# Ring_5_B.net
KiCad netlist of a schematic drawn in Altium Designer
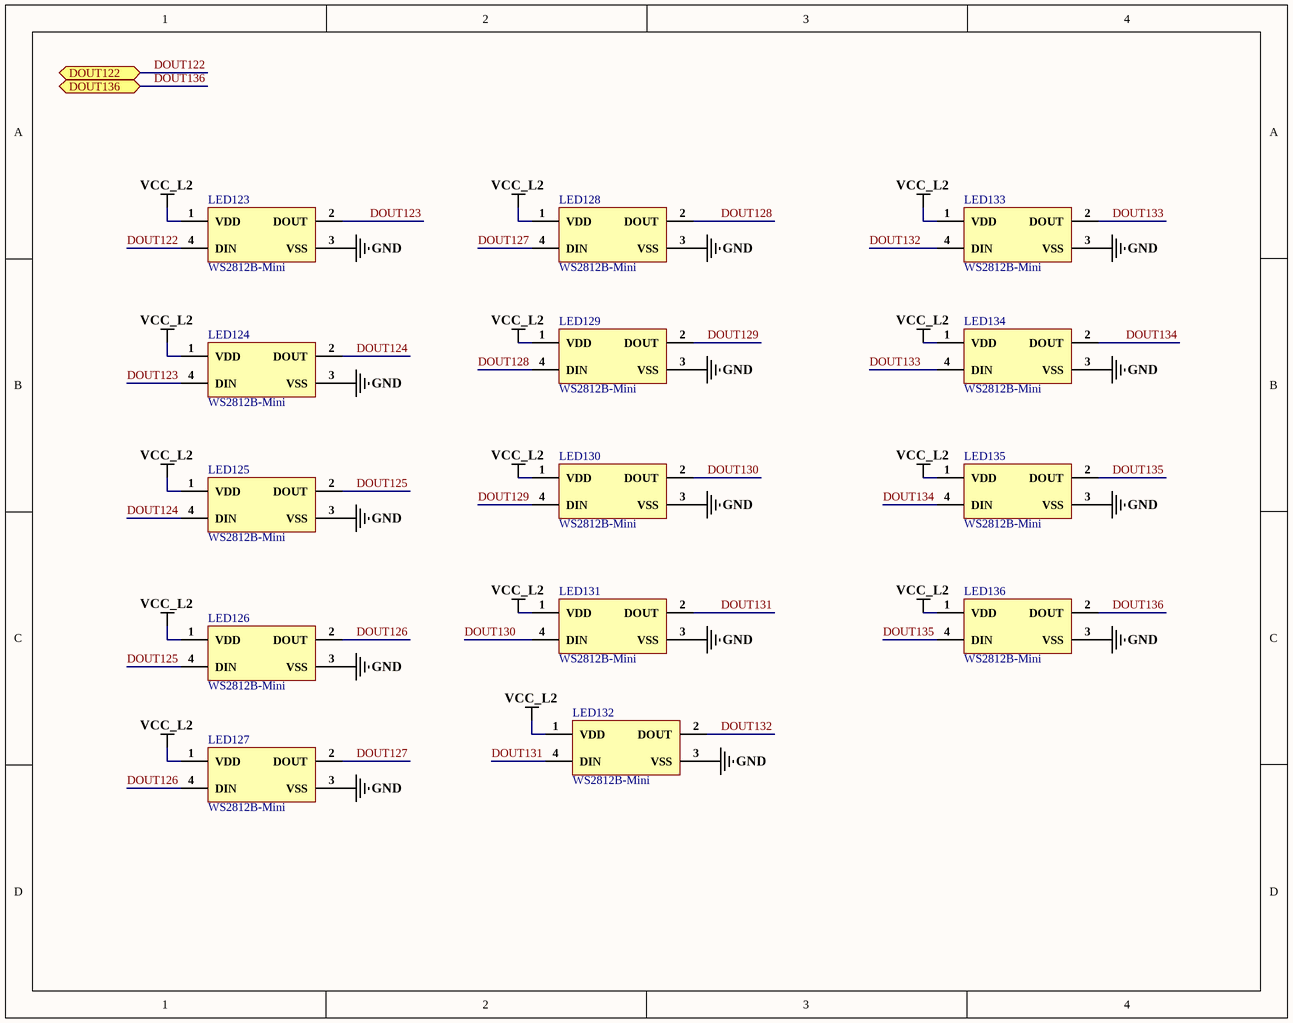
[diagram p0: Ring 5_B.SchDoc]

(export (version "E")
  (design (tool "Eeschema 10.0.6"))
  (components
    (comp (ref "LED123")
      (value "WS2812B-Mini")
      (footprint "WS2812B-Mini")
      (description "SMD,3.5x3.5mm Light Emitting Diodes (LED) RoHS")
      (fields (field (name "MANUFACTURER") "Worldsemi"))
      (libsource (lib "TT_IntLib") (part "WS2812B-Mini"))
    )
    (comp (ref "LED124")
      (value "WS2812B-Mini")
      (footprint "WS2812B-Mini")
      (description "SMD,3.5x3.5mm Light Emitting Diodes (LED) RoHS")
      (fields (field (name "MANUFACTURER") "Worldsemi"))
      (libsource (lib "TT_IntLib") (part "WS2812B-Mini"))
    )
    (comp (ref "LED125")
      (value "WS2812B-Mini")
      (footprint "WS2812B-Mini")
      (description "SMD,3.5x3.5mm Light Emitting Diodes (LED) RoHS")
      (fields (field (name "MANUFACTURER") "Worldsemi"))
      (libsource (lib "TT_IntLib") (part "WS2812B-Mini"))
    )
    (comp (ref "LED126")
      (value "WS2812B-Mini")
      (footprint "WS2812B-Mini")
      (description "SMD,3.5x3.5mm Light Emitting Diodes (LED) RoHS")
      (fields (field (name "MANUFACTURER") "Worldsemi"))
      (libsource (lib "TT_IntLib") (part "WS2812B-Mini"))
    )
    (comp (ref "LED127")
      (value "WS2812B-Mini")
      (footprint "WS2812B-Mini")
      (description "SMD,3.5x3.5mm Light Emitting Diodes (LED) RoHS")
      (fields (field (name "MANUFACTURER") "Worldsemi"))
      (libsource (lib "TT_IntLib") (part "WS2812B-Mini"))
    )
    (comp (ref "LED128")
      (value "WS2812B-Mini")
      (footprint "WS2812B-Mini")
      (description "SMD,3.5x3.5mm Light Emitting Diodes (LED) RoHS")
      (fields (field (name "MANUFACTURER") "Worldsemi"))
      (libsource (lib "TT_IntLib") (part "WS2812B-Mini"))
    )
    (comp (ref "LED129")
      (value "WS2812B-Mini")
      (footprint "WS2812B-Mini")
      (description "SMD,3.5x3.5mm Light Emitting Diodes (LED) RoHS")
      (fields (field (name "MANUFACTURER") "Worldsemi"))
      (libsource (lib "TT_IntLib") (part "WS2812B-Mini"))
    )
    (comp (ref "LED130")
      (value "WS2812B-Mini")
      (footprint "WS2812B-Mini")
      (description "SMD,3.5x3.5mm Light Emitting Diodes (LED) RoHS")
      (fields (field (name "MANUFACTURER") "Worldsemi"))
      (libsource (lib "TT_IntLib") (part "WS2812B-Mini"))
    )
    (comp (ref "LED131")
      (value "WS2812B-Mini")
      (footprint "WS2812B-Mini")
      (description "SMD,3.5x3.5mm Light Emitting Diodes (LED) RoHS")
      (fields (field (name "MANUFACTURER") "Worldsemi"))
      (libsource (lib "TT_IntLib") (part "WS2812B-Mini"))
    )
    (comp (ref "LED132")
      (value "WS2812B-Mini")
      (footprint "WS2812B-Mini")
      (description "SMD,3.5x3.5mm Light Emitting Diodes (LED) RoHS")
      (fields (field (name "MANUFACTURER") "Worldsemi"))
      (libsource (lib "TT_IntLib") (part "WS2812B-Mini"))
    )
    (comp (ref "LED133")
      (value "WS2812B-Mini")
      (footprint "WS2812B-Mini")
      (description "SMD,3.5x3.5mm Light Emitting Diodes (LED) RoHS")
      (fields (field (name "MANUFACTURER") "Worldsemi"))
      (libsource (lib "TT_IntLib") (part "WS2812B-Mini"))
    )
    (comp (ref "LED134")
      (value "WS2812B-Mini")
      (footprint "WS2812B-Mini")
      (description "SMD,3.5x3.5mm Light Emitting Diodes (LED) RoHS")
      (fields (field (name "MANUFACTURER") "Worldsemi"))
      (libsource (lib "TT_IntLib") (part "WS2812B-Mini"))
    )
    (comp (ref "LED135")
      (value "WS2812B-Mini")
      (footprint "WS2812B-Mini")
      (description "SMD,3.5x3.5mm Light Emitting Diodes (LED) RoHS")
      (fields (field (name "MANUFACTURER") "Worldsemi"))
      (libsource (lib "TT_IntLib") (part "WS2812B-Mini"))
    )
    (comp (ref "LED136")
      (value "WS2812B-Mini")
      (footprint "WS2812B-Mini")
      (description "SMD,3.5x3.5mm Light Emitting Diodes (LED) RoHS")
      (fields (field (name "MANUFACTURER") "Worldsemi"))
      (libsource (lib "TT_IntLib") (part "WS2812B-Mini"))
    )
  )
  (nets
    (net (code "1") (name "/DOUT122") (class "Default")
      (node (ref "LED123") (pin "4") (pinfunction "DIN_4") (pintype "passive"))
    )
    (net (code "2") (name "/DOUT123") (class "Default")
      (node (ref "LED123") (pin "2") (pinfunction "DOUT_2") (pintype "passive"))
      (node (ref "LED124") (pin "4") (pinfunction "DIN_4") (pintype "passive"))
    )
    (net (code "3") (name "/DOUT124") (class "Default")
      (node (ref "LED124") (pin "2") (pinfunction "DOUT_2") (pintype "passive"))
      (node (ref "LED125") (pin "4") (pinfunction "DIN_4") (pintype "passive"))
    )
    (net (code "4") (name "/DOUT125") (class "Default")
      (node (ref "LED125") (pin "2") (pinfunction "DOUT_2") (pintype "passive"))
      (node (ref "LED126") (pin "4") (pinfunction "DIN_4") (pintype "passive"))
    )
    (net (code "5") (name "/DOUT126") (class "Default")
      (node (ref "LED126") (pin "2") (pinfunction "DOUT_2") (pintype "passive"))
      (node (ref "LED127") (pin "4") (pinfunction "DIN_4") (pintype "passive"))
    )
    (net (code "6") (name "/DOUT127") (class "Default")
      (node (ref "LED127") (pin "2") (pinfunction "DOUT_2") (pintype "passive"))
      (node (ref "LED128") (pin "4") (pinfunction "DIN_4") (pintype "passive"))
    )
    (net (code "7") (name "/DOUT128") (class "Default")
      (node (ref "LED128") (pin "2") (pinfunction "DOUT_2") (pintype "passive"))
      (node (ref "LED129") (pin "4") (pinfunction "DIN_4") (pintype "passive"))
    )
    (net (code "8") (name "/DOUT129") (class "Default")
      (node (ref "LED129") (pin "2") (pinfunction "DOUT_2") (pintype "passive"))
      (node (ref "LED130") (pin "4") (pinfunction "DIN_4") (pintype "passive"))
    )
    (net (code "9") (name "/DOUT130") (class "Default")
      (node (ref "LED130") (pin "2") (pinfunction "DOUT_2") (pintype "passive"))
      (node (ref "LED131") (pin "4") (pinfunction "DIN_4") (pintype "passive"))
    )
    (net (code "10") (name "/DOUT131") (class "Default")
      (node (ref "LED131") (pin "2") (pinfunction "DOUT_2") (pintype "passive"))
      (node (ref "LED132") (pin "4") (pinfunction "DIN_4") (pintype "passive"))
    )
    (net (code "11") (name "/DOUT132") (class "Default")
      (node (ref "LED132") (pin "2") (pinfunction "DOUT_2") (pintype "passive"))
      (node (ref "LED133") (pin "4") (pinfunction "DIN_4") (pintype "passive"))
    )
    (net (code "12") (name "/DOUT133") (class "Default")
      (node (ref "LED133") (pin "2") (pinfunction "DOUT_2") (pintype "passive"))
      (node (ref "LED134") (pin "4") (pinfunction "DIN_4") (pintype "passive"))
    )
    (net (code "13") (name "/DOUT134") (class "Default")
      (node (ref "LED134") (pin "2") (pinfunction "DOUT_2") (pintype "passive"))
      (node (ref "LED135") (pin "4") (pinfunction "DIN_4") (pintype "passive"))
    )
    (net (code "14") (name "/DOUT135") (class "Default")
      (node (ref "LED135") (pin "2") (pinfunction "DOUT_2") (pintype "passive"))
      (node (ref "LED136") (pin "4") (pinfunction "DIN_4") (pintype "passive"))
    )
    (net (code "15") (name "/DOUT136") (class "Default")
      (node (ref "LED136") (pin "2") (pinfunction "DOUT_2") (pintype "passive"))
    )
    (net (code "16") (name "GND") (class "Default")
      (node (ref "LED123") (pin "3") (pinfunction "VSS_3") (pintype "passive"))
      (node (ref "LED124") (pin "3") (pinfunction "VSS_3") (pintype "passive"))
      (node (ref "LED125") (pin "3") (pinfunction "VSS_3") (pintype "passive"))
      (node (ref "LED126") (pin "3") (pinfunction "VSS_3") (pintype "passive"))
      (node (ref "LED127") (pin "3") (pinfunction "VSS_3") (pintype "passive"))
      (node (ref "LED128") (pin "3") (pinfunction "VSS_3") (pintype "passive"))
      (node (ref "LED129") (pin "3") (pinfunction "VSS_3") (pintype "passive"))
      (node (ref "LED130") (pin "3") (pinfunction "VSS_3") (pintype "passive"))
      (node (ref "LED131") (pin "3") (pinfunction "VSS_3") (pintype "passive"))
      (node (ref "LED132") (pin "3") (pinfunction "VSS_3") (pintype "passive"))
      (node (ref "LED133") (pin "3") (pinfunction "VSS_3") (pintype "passive"))
      (node (ref "LED134") (pin "3") (pinfunction "VSS_3") (pintype "passive"))
      (node (ref "LED135") (pin "3") (pinfunction "VSS_3") (pintype "passive"))
      (node (ref "LED136") (pin "3") (pinfunction "VSS_3") (pintype "passive"))
    )
    (net (code "17") (name "VCC_L2") (class "Default")
      (node (ref "LED123") (pin "1") (pinfunction "VDD_1") (pintype "passive"))
      (node (ref "LED124") (pin "1") (pinfunction "VDD_1") (pintype "passive"))
      (node (ref "LED125") (pin "1") (pinfunction "VDD_1") (pintype "passive"))
      (node (ref "LED126") (pin "1") (pinfunction "VDD_1") (pintype "passive"))
      (node (ref "LED127") (pin "1") (pinfunction "VDD_1") (pintype "passive"))
      (node (ref "LED128") (pin "1") (pinfunction "VDD_1") (pintype "passive"))
      (node (ref "LED129") (pin "1") (pinfunction "VDD_1") (pintype "passive"))
      (node (ref "LED130") (pin "1") (pinfunction "VDD_1") (pintype "passive"))
      (node (ref "LED131") (pin "1") (pinfunction "VDD_1") (pintype "passive"))
      (node (ref "LED132") (pin "1") (pinfunction "VDD_1") (pintype "passive"))
      (node (ref "LED133") (pin "1") (pinfunction "VDD_1") (pintype "passive"))
      (node (ref "LED134") (pin "1") (pinfunction "VDD_1") (pintype "passive"))
      (node (ref "LED135") (pin "1") (pinfunction "VDD_1") (pintype "passive"))
      (node (ref "LED136") (pin "1") (pinfunction "VDD_1") (pintype "passive"))
    )
  )
)
